# Schematic.net
KiCad netlist of a schematic drawn in Altium Designer
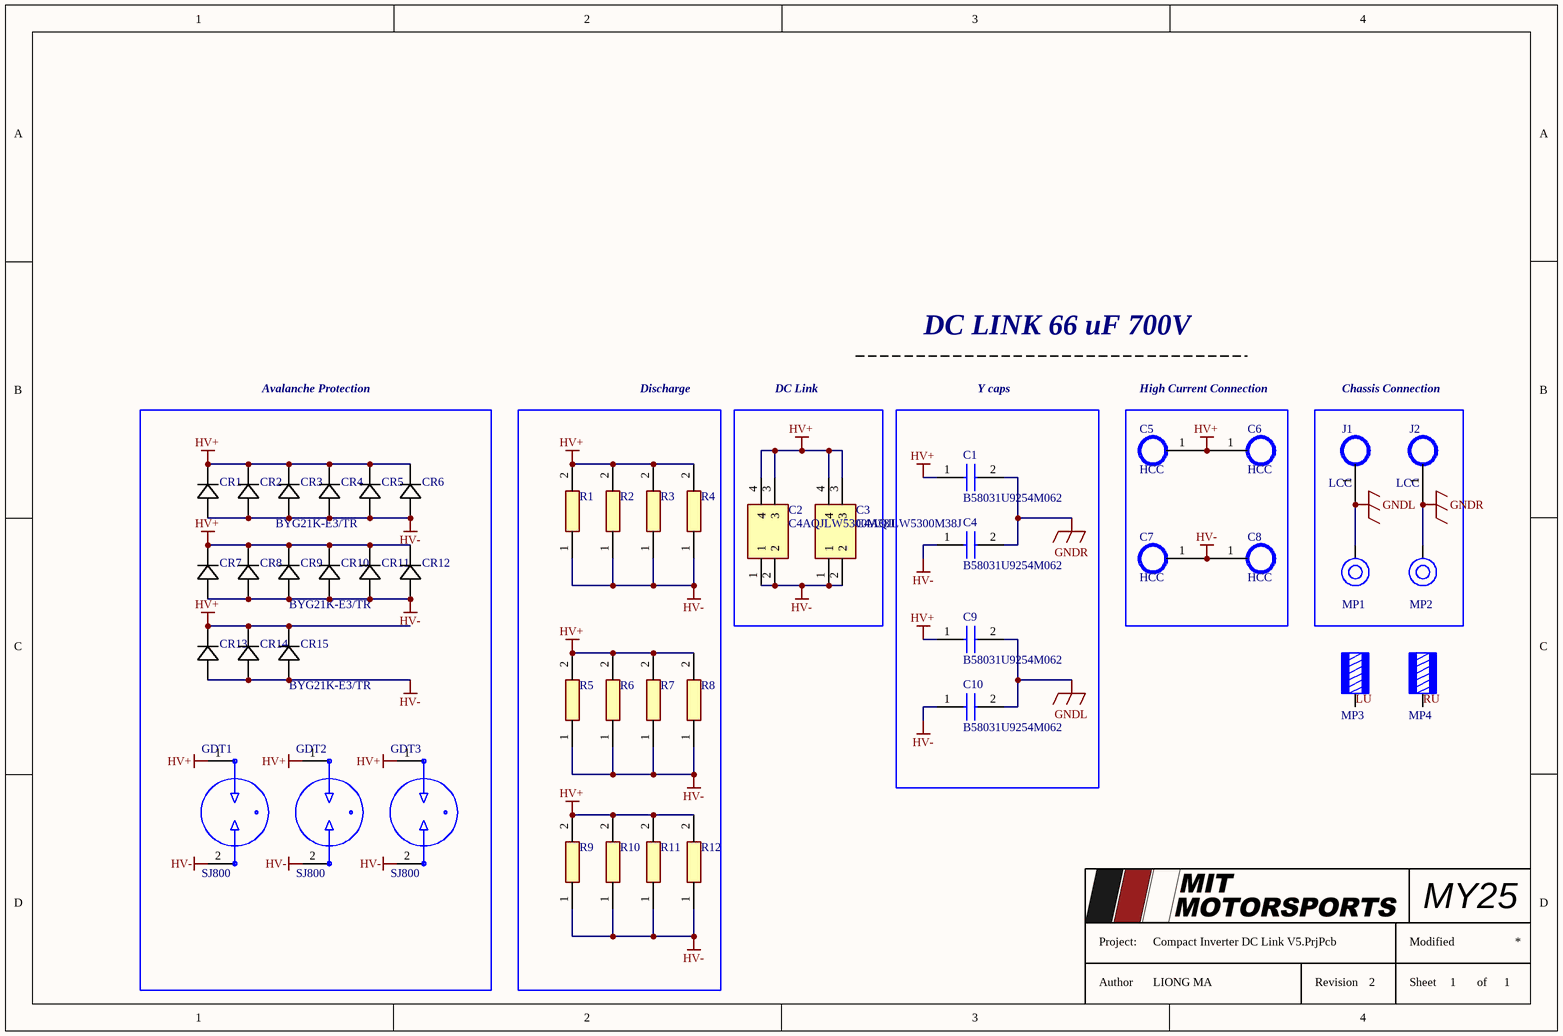
[diagram p0: Schematic.SchDoc]

(export (version "E")
  (design (tool "Eeschema 10.0.6"))
  (components
    (comp (ref "C1")
      (value "B58031U9254M062")
      (footprint "B58031U9254M062")
      (description "Capacitor")
      (fields (field (name "MOUSER PART NUMBER") "871-B58031U9254M062"))
      (libsource (lib "Schlib3") (part "B58031U9254M062"))
    )
    (comp (ref "C2")
      (value "C4AQJLW5300M38J")
      (footprint "PcbLib3:C4AQJLW5300M38J")
      (description "Capacitor")
      (fields (field (name "MOUSER PART NUMBER") "80-C4AQJLW5300M38J"))
      (libsource (lib "Schlib3") (part "C4AQJLW5300M38J"))
    )
    (comp (ref "C3")
      (value "C4AQJLW5300M38J")
      (footprint "PcbLib3:C4AQJLW5300M38J")
      (description "Capacitor")
      (fields (field (name "MOUSER PART NUMBER") "80-C4AQJLW5300M38J"))
      (libsource (lib "Schlib3") (part "C4AQJLW5300M38J"))
    )
    (comp (ref "C4")
      (value "B58031U9254M062")
      (footprint "B58031U9254M062")
      (description "Capacitor")
      (fields (field (name "MOUSER PART NUMBER") "871-B58031U9254M062"))
      (libsource (lib "Schlib3") (part "B58031U9254M062"))
    )
    (comp (ref "C5") (value "HCC") (footprint "6mm Pad") (libsource (lib "Schlib3") (part "HCC")))
    (comp (ref "C6") (value "HCC") (footprint "6mm Pad") (libsource (lib "Schlib3") (part "HCC")))
    (comp (ref "C7") (value "HCC") (footprint "6mm Pad") (libsource (lib "Schlib3") (part "HCC")))
    (comp (ref "C8") (value "HCC") (footprint "6mm Pad") (libsource (lib "Schlib3") (part "HCC")))
    (comp (ref "C9")
      (value "B58031U9254M062")
      (footprint "B58031U9254M062")
      (description "Capacitor")
      (fields (field (name "MOUSER PART NUMBER") "871-B58031U9254M062"))
      (libsource (lib "Schlib3") (part "B58031U9254M062"))
    )
    (comp (ref "C10")
      (value "B58031U9254M062")
      (footprint "B58031U9254M062")
      (description "Capacitor")
      (fields (field (name "MOUSER PART NUMBER") "871-B58031U9254M062"))
      (libsource (lib "Schlib3") (part "B58031U9254M062"))
    )
    (comp (ref "CR1")
      (value "BYG21K-E3/TR")
      (footprint "DO-214AC_VIS")
      (description "1.5A,800V,120nS FS AVALANCHE SMD")
      (fields (field (name "COPYRIGHT") "Copyright (C) 2025 Ultra Librarian. All rights reserved."))
      (libsource (lib "Schlib3") (part "BYG21K-E3TR"))
    )
    (comp (ref "CR2")
      (value "BYG21K-E3/TR")
      (footprint "DO-214AC_VIS")
      (description "1.5A,800V,120nS FS AVALANCHE SMD")
      (fields (field (name "COPYRIGHT") "Copyright (C) 2025 Ultra Librarian. All rights reserved."))
      (libsource (lib "Schlib3") (part "BYG21K-E3TR"))
    )
    (comp (ref "CR3")
      (value "BYG21K-E3/TR")
      (footprint "DO-214AC_VIS")
      (description "1.5A,800V,120nS FS AVALANCHE SMD")
      (fields (field (name "COPYRIGHT") "Copyright (C) 2025 Ultra Librarian. All rights reserved."))
      (libsource (lib "Schlib3") (part "BYG21K-E3TR"))
    )
    (comp (ref "CR4")
      (value "BYG21K-E3/TR")
      (footprint "DO-214AC_VIS")
      (description "1.5A,800V,120nS FS AVALANCHE SMD")
      (fields (field (name "COPYRIGHT") "Copyright (C) 2025 Ultra Librarian. All rights reserved."))
      (libsource (lib "Schlib3") (part "BYG21K-E3TR"))
    )
    (comp (ref "CR5")
      (value "BYG21K-E3/TR")
      (footprint "DO-214AC_VIS")
      (description "1.5A,800V,120nS FS AVALANCHE SMD")
      (fields (field (name "COPYRIGHT") "Copyright (C) 2025 Ultra Librarian. All rights reserved."))
      (libsource (lib "Schlib3") (part "BYG21K-E3TR"))
    )
    (comp (ref "CR6")
      (value "BYG21K-E3/TR")
      (footprint "DO-214AC_VIS")
      (description "1.5A,800V,120nS FS AVALANCHE SMD")
      (fields (field (name "COPYRIGHT") "Copyright (C) 2025 Ultra Librarian. All rights reserved."))
      (libsource (lib "Schlib3") (part "BYG21K-E3TR"))
    )
    (comp (ref "CR7")
      (value "BYG21K-E3/TR")
      (footprint "DO-214AC_VIS")
      (description "1.5A,800V,120nS FS AVALANCHE SMD")
      (fields (field (name "COPYRIGHT") "Copyright (C) 2025 Ultra Librarian. All rights reserved."))
      (libsource (lib "Schlib3") (part "BYG21K-E3TR"))
    )
    (comp (ref "CR8")
      (value "BYG21K-E3/TR")
      (footprint "DO-214AC_VIS")
      (description "1.5A,800V,120nS FS AVALANCHE SMD")
      (fields (field (name "COPYRIGHT") "Copyright (C) 2025 Ultra Librarian. All rights reserved."))
      (libsource (lib "Schlib3") (part "BYG21K-E3TR"))
    )
    (comp (ref "CR9")
      (value "BYG21K-E3/TR")
      (footprint "DO-214AC_VIS")
      (description "1.5A,800V,120nS FS AVALANCHE SMD")
      (fields (field (name "COPYRIGHT") "Copyright (C) 2025 Ultra Librarian. All rights reserved."))
      (libsource (lib "Schlib3") (part "BYG21K-E3TR"))
    )
    (comp (ref "CR10")
      (value "BYG21K-E3/TR")
      (footprint "DO-214AC_VIS")
      (description "1.5A,800V,120nS FS AVALANCHE SMD")
      (fields (field (name "COPYRIGHT") "Copyright (C) 2025 Ultra Librarian. All rights reserved."))
      (libsource (lib "Schlib3") (part "BYG21K-E3TR"))
    )
    (comp (ref "CR11")
      (value "BYG21K-E3/TR")
      (footprint "DO-214AC_VIS")
      (description "1.5A,800V,120nS FS AVALANCHE SMD")
      (fields (field (name "COPYRIGHT") "Copyright (C) 2025 Ultra Librarian. All rights reserved."))
      (libsource (lib "Schlib3") (part "BYG21K-E3TR"))
    )
    (comp (ref "CR12")
      (value "BYG21K-E3/TR")
      (footprint "DO-214AC_VIS")
      (description "1.5A,800V,120nS FS AVALANCHE SMD")
      (fields (field (name "COPYRIGHT") "Copyright (C) 2025 Ultra Librarian. All rights reserved."))
      (libsource (lib "Schlib3") (part "BYG21K-E3TR"))
    )
    (comp (ref "CR13")
      (value "BYG21K-E3/TR")
      (footprint "DO-214AC_VIS")
      (description "1.5A,800V,120nS FS AVALANCHE SMD")
      (fields (field (name "COPYRIGHT") "Copyright (C) 2025 Ultra Librarian. All rights reserved."))
      (libsource (lib "Schlib3") (part "BYG21K-E3TR"))
    )
    (comp (ref "CR14")
      (value "BYG21K-E3/TR")
      (footprint "DO-214AC_VIS")
      (description "1.5A,800V,120nS FS AVALANCHE SMD")
      (fields (field (name "COPYRIGHT") "Copyright (C) 2025 Ultra Librarian. All rights reserved."))
      (libsource (lib "Schlib3") (part "BYG21K-E3TR"))
    )
    (comp (ref "CR15")
      (value "BYG21K-E3/TR")
      (footprint "DO-214AC_VIS")
      (description "1.5A,800V,120nS FS AVALANCHE SMD")
      (fields (field (name "COPYRIGHT") "Copyright (C) 2025 Ultra Librarian. All rights reserved."))
      (libsource (lib "Schlib3") (part "BYG21K-E3TR"))
    )
    (comp (ref "GDT1")
      (value "SJ800")
      (footprint "PcbLib3:SJ1000")
      (description "Gas Discharge Tube")
      (libsource (lib "*") (part "SJ800"))
    )
    (comp (ref "GDT2")
      (value "SJ800")
      (footprint "PcbLib3:SJ1000")
      (description "Gas Discharge Tube")
      (libsource (lib "*") (part "SJ800"))
    )
    (comp (ref "GDT3")
      (value "SJ800")
      (footprint "PcbLib3:SJ1000")
      (description "Gas Discharge Tube")
      (libsource (lib "*") (part "SJ800"))
    )
    (comp (ref "J1") (value "LCC") (footprint "PAD 3MM") (libsource (lib "Schlib3") (part "LCC")))
    (comp (ref "J2") (value "LCC") (footprint "PAD 3MM") (libsource (lib "Schlib3") (part "LCC")))
    (comp (ref "MP1")
      (value "M3 x 2.6mm")
      (footprint "9775026360")
      (description "WA-SMSR SMT Steel Spacer Reverse, M3 x 2.6mm")
      (fields
        (field (name "MANUFACTURER PART NUMBER") "9775026360R")
        (field (name "MANUFACTURER") "Wurth Elektronik")
      )
      (libsource (lib "Schlib3") (part "9775026360R"))
    )
    (comp (ref "MP2")
      (value "M3 x 2.6mm")
      (footprint "9775026360")
      (description "WA-SMSR SMT Steel Spacer Reverse, M3 x 2.6mm")
      (fields
        (field (name "MANUFACTURER PART NUMBER") "9775026360R")
        (field (name "MANUFACTURER") "Wurth Elektronik")
      )
      (libsource (lib "Schlib3") (part "9775026360R"))
    )
    (comp (ref "MP3")
      (value "M3")
      (footprint "7466313")
      (description "WP-SMRA REDCUBE SMT Right Angled with pins, M3, 50A")
      (fields
        (field (name "MANUFACTURER PART NUMBER") "7466313R")
        (field (name "MANUFACTURER") "Wurth Elektronik")
      )
      (libsource (lib "Schlib3") (part "7466313R"))
    )
    (comp (ref "MP4")
      (value "M3")
      (footprint "7466313")
      (description "WP-SMRA REDCUBE SMT Right Angled with pins, M3, 50A")
      (fields
        (field (name "MANUFACTURER PART NUMBER") "7466313R")
        (field (name "MANUFACTURER") "Wurth Elektronik")
      )
      (libsource (lib "Schlib3") (part "7466313R"))
    )
    (comp (ref "R1")
      (value "CHV2512-JW-105ELF")
      (footprint "PcbLib3:RESC6432X75N")
      (description "Resistor")
      (fields (field (name "MOUSER PART NUMBER") "652-CHV2512JW105ELF"))
      (libsource (lib "Schlib3") (part "CHV2512-JW-105ELF"))
    )
    (comp (ref "R2")
      (value "CHV2512-JW-105ELF")
      (footprint "PcbLib3:RESC6432X75N")
      (description "Resistor")
      (fields (field (name "MOUSER PART NUMBER") "652-CHV2512JW105ELF"))
      (libsource (lib "Schlib3") (part "CHV2512-JW-105ELF"))
    )
    (comp (ref "R3")
      (value "CHV2512-JW-105ELF")
      (footprint "PcbLib3:RESC6432X75N")
      (description "Resistor")
      (fields (field (name "MOUSER PART NUMBER") "652-CHV2512JW105ELF"))
      (libsource (lib "Schlib3") (part "CHV2512-JW-105ELF"))
    )
    (comp (ref "R4")
      (value "CHV2512-JW-105ELF")
      (footprint "PcbLib3:RESC6432X75N")
      (description "Resistor")
      (fields (field (name "MOUSER PART NUMBER") "652-CHV2512JW105ELF"))
      (libsource (lib "Schlib3") (part "CHV2512-JW-105ELF"))
    )
    (comp (ref "R5")
      (value "CHV2512-JW-105ELF")
      (footprint "PcbLib3:RESC6432X75N")
      (description "Resistor")
      (fields (field (name "MOUSER PART NUMBER") "652-CHV2512JW105ELF"))
      (libsource (lib "Schlib3") (part "CHV2512-JW-105ELF"))
    )
    (comp (ref "R6")
      (value "CHV2512-JW-105ELF")
      (footprint "PcbLib3:RESC6432X75N")
      (description "Resistor")
      (fields (field (name "MOUSER PART NUMBER") "652-CHV2512JW105ELF"))
      (libsource (lib "Schlib3") (part "CHV2512-JW-105ELF"))
    )
    (comp (ref "R7")
      (value "CHV2512-JW-105ELF")
      (footprint "PcbLib3:RESC6432X75N")
      (description "Resistor")
      (fields (field (name "MOUSER PART NUMBER") "652-CHV2512JW105ELF"))
      (libsource (lib "Schlib3") (part "CHV2512-JW-105ELF"))
    )
    (comp (ref "R8")
      (value "CHV2512-JW-105ELF")
      (footprint "PcbLib3:RESC6432X75N")
      (description "Resistor")
      (fields (field (name "MOUSER PART NUMBER") "652-CHV2512JW105ELF"))
      (libsource (lib "Schlib3") (part "CHV2512-JW-105ELF"))
    )
    (comp (ref "R9")
      (value "CHV2512-JW-105ELF")
      (footprint "PcbLib3:RESC6432X75N")
      (description "Resistor")
      (fields (field (name "MOUSER PART NUMBER") "652-CHV2512JW105ELF"))
      (libsource (lib "Schlib3") (part "CHV2512-JW-105ELF"))
    )
    (comp (ref "R10")
      (value "CHV2512-JW-105ELF")
      (footprint "PcbLib3:RESC6432X75N")
      (description "Resistor")
      (fields (field (name "MOUSER PART NUMBER") "652-CHV2512JW105ELF"))
      (libsource (lib "Schlib3") (part "CHV2512-JW-105ELF"))
    )
    (comp (ref "R11")
      (value "CHV2512-JW-105ELF")
      (footprint "PcbLib3:RESC6432X75N")
      (description "Resistor")
      (fields (field (name "MOUSER PART NUMBER") "652-CHV2512JW105ELF"))
      (libsource (lib "Schlib3") (part "CHV2512-JW-105ELF"))
    )
    (comp (ref "R12")
      (value "CHV2512-JW-105ELF")
      (footprint "PcbLib3:RESC6432X75N")
      (description "Resistor")
      (fields (field (name "MOUSER PART NUMBER") "652-CHV2512JW105ELF"))
      (libsource (lib "Schlib3") (part "CHV2512-JW-105ELF"))
    )
  )
  (nets
    (net (code "1") (name "/LU") (class "Default")
      (node (ref "MP3") (pin "1") (pinfunction "1_1") (pintype "passive"))
    )
    (net (code "2") (name "/RU") (class "Default")
      (node (ref "MP4") (pin "1") (pinfunction "1_1") (pintype "passive"))
    )
    (net (code "3") (name "GNDL") (class "Default")
      (node (ref "C10") (pin "2") (pinfunction "2_2") (pintype "passive"))
      (node (ref "C9") (pin "2") (pinfunction "2_2") (pintype "passive"))
      (node (ref "J1") (pin "1") (pintype "passive"))
      (node (ref "MP1") (pin "1") (pinfunction "1_1") (pintype "passive"))
    )
    (net (code "4") (name "GNDR") (class "Default")
      (node (ref "C1") (pin "2") (pinfunction "2_2") (pintype "passive"))
      (node (ref "C4") (pin "2") (pinfunction "2_2") (pintype "passive"))
      (node (ref "J2") (pin "1") (pintype "passive"))
      (node (ref "MP2") (pin "1") (pinfunction "1_1") (pintype "passive"))
    )
    (net (code "5") (name "HV+") (class "Default")
      (node (ref "C1") (pin "1") (pinfunction "1_1") (pintype "passive"))
      (node (ref "C2") (pin "3") (pinfunction "3_3") (pintype "passive"))
      (node (ref "C2") (pin "4") (pinfunction "4_4") (pintype "passive"))
      (node (ref "C3") (pin "3") (pinfunction "3_3") (pintype "passive"))
      (node (ref "C3") (pin "4") (pinfunction "4_4") (pintype "passive"))
      (node (ref "C5") (pin "1") (pintype "passive"))
      (node (ref "C6") (pin "1") (pintype "passive"))
      (node (ref "C9") (pin "1") (pinfunction "1_1") (pintype "passive"))
      (node (ref "CR1") (pin "1") (pinfunction "1_1") (pintype "passive"))
      (node (ref "CR10") (pin "1") (pinfunction "1_1") (pintype "passive"))
      (node (ref "CR11") (pin "1") (pinfunction "1_1") (pintype "passive"))
      (node (ref "CR12") (pin "1") (pinfunction "1_1") (pintype "passive"))
      (node (ref "CR13") (pin "1") (pinfunction "1_1") (pintype "passive"))
      (node (ref "CR14") (pin "1") (pinfunction "1_1") (pintype "passive"))
      (node (ref "CR15") (pin "1") (pinfunction "1_1") (pintype "passive"))
      (node (ref "CR2") (pin "1") (pinfunction "1_1") (pintype "passive"))
      (node (ref "CR3") (pin "1") (pinfunction "1_1") (pintype "passive"))
      (node (ref "CR4") (pin "1") (pinfunction "1_1") (pintype "passive"))
      (node (ref "CR5") (pin "1") (pinfunction "1_1") (pintype "passive"))
      (node (ref "CR6") (pin "1") (pinfunction "1_1") (pintype "passive"))
      (node (ref "CR7") (pin "1") (pinfunction "1_1") (pintype "passive"))
      (node (ref "CR8") (pin "1") (pinfunction "1_1") (pintype "passive"))
      (node (ref "CR9") (pin "1") (pinfunction "1_1") (pintype "passive"))
      (node (ref "GDT1") (pin "1") (pinfunction "1_1") (pintype "passive"))
      (node (ref "GDT2") (pin "1") (pinfunction "1_1") (pintype "passive"))
      (node (ref "GDT3") (pin "1") (pinfunction "1_1") (pintype "passive"))
      (node (ref "R1") (pin "2") (pinfunction "2_2") (pintype "passive"))
      (node (ref "R10") (pin "2") (pinfunction "2_2") (pintype "passive"))
      (node (ref "R11") (pin "2") (pinfunction "2_2") (pintype "passive"))
      (node (ref "R12") (pin "2") (pinfunction "2_2") (pintype "passive"))
      (node (ref "R2") (pin "2") (pinfunction "2_2") (pintype "passive"))
      (node (ref "R3") (pin "2") (pinfunction "2_2") (pintype "passive"))
      (node (ref "R4") (pin "2") (pinfunction "2_2") (pintype "passive"))
      (node (ref "R5") (pin "2") (pinfunction "2_2") (pintype "passive"))
      (node (ref "R6") (pin "2") (pinfunction "2_2") (pintype "passive"))
      (node (ref "R7") (pin "2") (pinfunction "2_2") (pintype "passive"))
      (node (ref "R8") (pin "2") (pinfunction "2_2") (pintype "passive"))
      (node (ref "R9") (pin "2") (pinfunction "2_2") (pintype "passive"))
    )
    (net (code "6") (name "HV-") (class "Default")
      (node (ref "C10") (pin "1") (pinfunction "1_1") (pintype "passive"))
      (node (ref "C2") (pin "1") (pinfunction "1_1") (pintype "passive"))
      (node (ref "C2") (pin "2") (pinfunction "2_2") (pintype "passive"))
      (node (ref "C3") (pin "1") (pinfunction "1_1") (pintype "passive"))
      (node (ref "C3") (pin "2") (pinfunction "2_2") (pintype "passive"))
      (node (ref "C4") (pin "1") (pinfunction "1_1") (pintype "passive"))
      (node (ref "C7") (pin "1") (pintype "passive"))
      (node (ref "C8") (pin "1") (pintype "passive"))
      (node (ref "CR1") (pin "2") (pinfunction "2_2") (pintype "passive"))
      (node (ref "CR10") (pin "2") (pinfunction "2_2") (pintype "passive"))
      (node (ref "CR11") (pin "2") (pinfunction "2_2") (pintype "passive"))
      (node (ref "CR12") (pin "2") (pinfunction "2_2") (pintype "passive"))
      (node (ref "CR13") (pin "2") (pinfunction "2_2") (pintype "passive"))
      (node (ref "CR14") (pin "2") (pinfunction "2_2") (pintype "passive"))
      (node (ref "CR15") (pin "2") (pinfunction "2_2") (pintype "passive"))
      (node (ref "CR2") (pin "2") (pinfunction "2_2") (pintype "passive"))
      (node (ref "CR3") (pin "2") (pinfunction "2_2") (pintype "passive"))
      (node (ref "CR4") (pin "2") (pinfunction "2_2") (pintype "passive"))
      (node (ref "CR5") (pin "2") (pinfunction "2_2") (pintype "passive"))
      (node (ref "CR6") (pin "2") (pinfunction "2_2") (pintype "passive"))
      (node (ref "CR7") (pin "2") (pinfunction "2_2") (pintype "passive"))
      (node (ref "CR8") (pin "2") (pinfunction "2_2") (pintype "passive"))
      (node (ref "CR9") (pin "2") (pinfunction "2_2") (pintype "passive"))
      (node (ref "GDT1") (pin "2") (pinfunction "2_2") (pintype "passive"))
      (node (ref "GDT2") (pin "2") (pinfunction "2_2") (pintype "passive"))
      (node (ref "GDT3") (pin "2") (pinfunction "2_2") (pintype "passive"))
      (node (ref "R1") (pin "1") (pinfunction "1_1") (pintype "passive"))
      (node (ref "R10") (pin "1") (pinfunction "1_1") (pintype "passive"))
      (node (ref "R11") (pin "1") (pinfunction "1_1") (pintype "passive"))
      (node (ref "R12") (pin "1") (pinfunction "1_1") (pintype "passive"))
      (node (ref "R2") (pin "1") (pinfunction "1_1") (pintype "passive"))
      (node (ref "R3") (pin "1") (pinfunction "1_1") (pintype "passive"))
      (node (ref "R4") (pin "1") (pinfunction "1_1") (pintype "passive"))
      (node (ref "R5") (pin "1") (pinfunction "1_1") (pintype "passive"))
      (node (ref "R6") (pin "1") (pinfunction "1_1") (pintype "passive"))
      (node (ref "R7") (pin "1") (pinfunction "1_1") (pintype "passive"))
      (node (ref "R8") (pin "1") (pinfunction "1_1") (pintype "passive"))
      (node (ref "R9") (pin "1") (pinfunction "1_1") (pintype "passive"))
    )
  )
)
